# 02_Power_path.net
KiCad netlist of a schematic drawn in Altium Designer
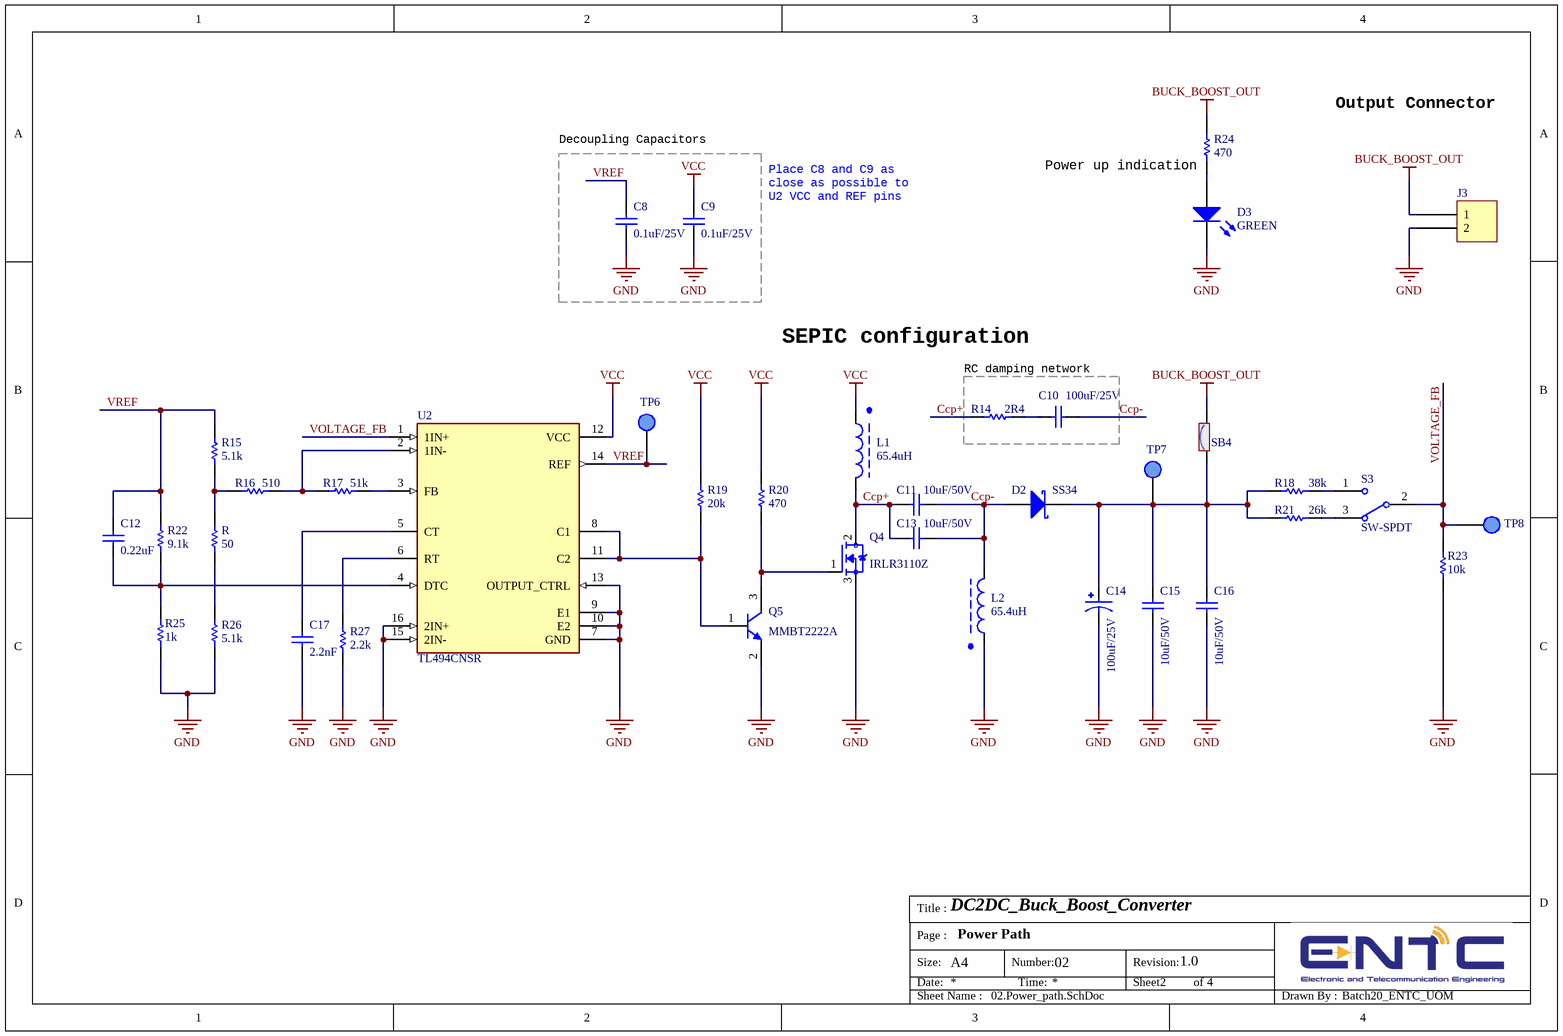
[diagram p0: 02.Power_path.SchDoc]

(export (version "E")
  (design (tool "Eeschema 10.0.6"))
  (components
    (comp (ref "C8")
      (value "0.1uF/25V")
      (footprint "cap0805")
      (fields (field (name "MF") "KYOCERA AVX") (field (name "MP") "08053C104K4Z2A"))
      (libsource (lib "Altium_Main_Library") (part "Cap"))
    )
    (comp (ref "C9")
      (value "0.1uF/25V")
      (footprint "cap0805")
      (fields (field (name "MF") "KYOCERA AVX") (field (name "MP") "08053C104K4Z2A"))
      (libsource (lib "Altium_Main_Library") (part "Cap"))
    )
    (comp (ref "C10")
      (value "100uF/25V")
      (footprint "cap0805")
      (description "Capacitor")
      (libsource (lib "Altium_Main_Library") (part "Cap"))
    )
    (comp (ref "C11")
      (value "10uF/50V")
      (footprint "cap0805")
      (description "Multilayer Ceramic Capacitors MLCC - SMD/SMT 10 uF 50 VDC 10% 0805 X5R")
      (fields (field (name "MF") "Murata Electronics") (field (name "MP") "GRM21BR61H106KE43L"))
      (libsource (lib "Altium_Main_Library") (part "Cap"))
    )
    (comp (ref "C12")
      (value "0.22uF")
      (footprint "cap0805")
      (fields (field (name "MF") "KYOCERA AVX") (field (name "MP") "08055C224KAT2A"))
      (libsource (lib "Altium_Main_Library") (part "Cap"))
    )
    (comp (ref "C13")
      (value "10uF/50V")
      (footprint "cap0805")
      (description "Multilayer Ceramic Capacitors MLCC - SMD/SMT 10 uF 50 VDC 10% 0805 X5R")
      (fields (field (name "MF") "Murata Electronics") (field (name "MP") "GRM21BR61H106KE43L"))
      (libsource (lib "Altium_Main_Library") (part "Cap"))
    )
    (comp (ref "C14")
      (value "100uF/25V")
      (footprint "CAP_EEEFC0J680P")
      (description "Aluminum Electrolytic Capacitors - SMD WCAP-ASLU 100uF 25V 20% SMD/SMT")
      (fields (field (name "MP") "865090449009") (field (name "MF") "Wurth Elektronik"))
      (libsource (lib "Altium_Main_Library") (part "Cap Pol"))
    )
    (comp (ref "C15")
      (value "10uF/50V")
      (footprint "cap0805")
      (description "Multilayer Ceramic Capacitors MLCC - SMD/SMT 10 uF 50 VDC 10% 0805 X5R")
      (fields (field (name "MF") "Murata Electronics") (field (name "MP") "GRM21BR61H106KE43L"))
      (libsource (lib "Altium_Main_Library") (part "Cap"))
    )
    (comp (ref "C16")
      (value "10uF/50V")
      (footprint "cap0805")
      (description "Multilayer Ceramic Capacitors MLCC - SMD/SMT 10 uF 50 VDC 10% 0805 X5R")
      (fields (field (name "MF") "Murata Electronics") (field (name "MP") "GRM21BR61H106KE43L"))
      (libsource (lib "Altium_Main_Library") (part "Cap"))
    )
    (comp (ref "C17")
      (value "2.2nF")
      (footprint "cap0805")
      (fields (field (name "MF") "KYOCERA AVX") (field (name "MP") "08055C222J4T2A"))
      (libsource (lib "Altium_Main_Library") (part "Cap"))
    )
    (comp (ref "D2")
      (value "SS34")
      (footprint "DIO_SS34")
      (description "Schottky Diodes & Rectifiers 40V 3A")
      (fields (field (name "MP") "B340-13-F") (field (name "MF") "Diodes Incorporated"))
      (libsource (lib "DC2DC_Buck_Boost_Converter_SchLib") (part "D Schottky"))
    )
    (comp (ref "D3")
      (value "GREEN")
      (footprint "LED0805")
      (description "Standard LEDs - SMD Ultra Green, 574nm 2.2V, 45mcd")
      (fields (field (name "MP") "SML-LX0805SUGC-TR") (field (name "MF") "Lumex"))
      (libsource (lib "Altium_Main_Library") (part "LED"))
    )
    (comp (ref "J3")
      (value "~")
      (footprint "JST XH B2B-XH-A")
      (description "Barrier Terminal Blocks NC6-P108-02")
      (fields (field (name "MP") "NC6-P108-02") (field (name "MF") "TE Connectivity"))
      (libsource (lib "Altium_Main_Library") (part "2 Pin"))
    )
    (comp (ref "L1")
      (value "65.4uH")
      (footprint "toroid-16x8")
      (description "Inductor")
      (libsource (lib "DC2DC_Buck_Boost_Converter_SchLib") (part "Inductor-ferrite core"))
    )
    (comp (ref "L2")
      (value "65.4uH")
      (footprint "toroid-16x8")
      (description "Inductor")
      (libsource (lib "DC2DC_Buck_Boost_Converter_SchLib") (part "Inductor-ferrite core"))
    )
    (comp (ref "Q4")
      (value "IRLR3110Z")
      (footprint "TO252")
      (description "MOSFETs MOSFT 100V 63A 14mOhm 34nC Log Lvl")
      (fields (field (name "MP") "IRLR3110ZTRLPBF") (field (name "MF") "Infineon Technologies"))
      (libsource (lib "DC2DC_Buck_Boost_Converter_SchLib") (part "IRLR3110Z"))
    )
    (comp (ref "Q5")
      (value "MMBT2222A")
      (footprint "SOT23")
      (description "Bipolar Transistors - BJT BJT, SOT-23, 40V, 600mA, NPN")
      (fields (field (name "MF") "Diotec Semiconductor"))
      (libsource (lib "Altium_Main_Library") (part "NPN"))
    )
    (comp (ref "R")
      (value "50")
      (footprint "RES0402")
      (description "Resistor")
      (libsource (lib "Altium_Main_Library") (part "Res"))
    )
    (comp (ref "R14")
      (value "2R4")
      (footprint "RES0805")
      (description "Thick Film Resistors - SMD 1/4W 0.05 2.4R")
      (fields (field (name "MP") "CRCW08052R40FKEA") (field (name "MF") "Vishay / Dale"))
      (libsource (lib "Altium_Main_Library") (part "Res"))
    )
    (comp (ref "R15")
      (value "5.1k")
      (footprint "RES0805")
      (description "Thick Film Resistors - SMD 5.1Kohms 1% 100ppm")
      (fields (field (name "MP") "RCA08055K10FKEA") (field (name "MF") "Vishay / Draloric"))
      (libsource (lib "Altium_Main_Library") (part "Res"))
    )
    (comp (ref "R16")
      (value "510")
      (footprint "RES0805")
      (description "Thick Film Resistors - SMD 510ohm 5%")
      (fields (field (name "MP") "CR0805-JW-511ELF") (field (name "MF") "Bourns"))
      (libsource (lib "Altium_Main_Library") (part "Res"))
    )
    (comp (ref "R17")
      (value "51k")
      (footprint "RES0805")
      (description "Thick Film Resistors - SMD 51K 1%")
      (fields (field (name "MP") "CR0805-FX-5102ELF") (field (name "MF") "Bourns"))
      (libsource (lib "Altium_Main_Library") (part "Res"))
    )
    (comp (ref "R18")
      (value "38k")
      (footprint "RES0805")
      (description "Thick Film Resistors - SMD CRCW0805 38K 1% 100 RT1")
      (fields (field (name "MP") "CRCW080538K0FKTA") (field (name "MF") "Vishay / Dale"))
      (libsource (lib "Altium_Main_Library") (part "Res"))
    )
    (comp (ref "R19")
      (value "20k")
      (footprint "RES0805")
      (description "Thick Film Resistors - SMD 20K 1%")
      (fields (field (name "MP") "CR0805-FX-2002ELF") (field (name "MF") "Bourns"))
      (libsource (lib "Altium_Main_Library") (part "Res"))
    )
    (comp (ref "R20")
      (value "470")
      (footprint "res1206")
      (description "Thick Film Resistors - SMD 470ohm 5%")
      (fields (field (name "MP") "CR1206-JW-471ELF") (field (name "MF") "Bourns"))
      (libsource (lib "Altium_Main_Library") (part "Res"))
    )
    (comp (ref "R21")
      (value "26k")
      (footprint "RES0805")
      (description "Thick Film Resistors - SMD 26.1K 1%")
      (fields (field (name "MP") "CR0805-FX-2612ELF") (field (name "MF") "Bourns"))
      (libsource (lib "Altium_Main_Library") (part "Res"))
    )
    (comp (ref "R22")
      (value "9.1k")
      (footprint "RES0805")
      (description "Thick Film Resistors - SMD 9.1K 1%")
      (fields (field (name "MP") "CR0805-FX-9101ELF") (field (name "MF") "Bourns"))
      (libsource (lib "Altium_Main_Library") (part "Res"))
    )
    (comp (ref "R23")
      (value "10k")
      (footprint "RES0805")
      (description "Thin Film Resistors - SMD ResThinFilm 0805 10kR 0.5% 125mW TC25")
      (fields (field (name "MP") "CRT0805ADY-1002ELF") (field (name "MF") "Bourns"))
      (libsource (lib "Altium_Main_Library") (part "Res"))
    )
    (comp (ref "R24")
      (value "470")
      (footprint "RES0805")
      (description "Thick Film Resistors - SMD 470ohm 5%")
      (fields (field (name "MP") "CR0805-JW-471ELF") (field (name "MF") "Bourns"))
      (libsource (lib "Altium_Main_Library") (part "Res"))
    )
    (comp (ref "R25")
      (value "1k")
      (footprint "RES0805")
      (description "Thick Film Resistors - SMD 1 kOhms 125 mW 0805 1%")
      (fields (field (name "MP") "RC0805FR-071KL") (field (name "MF") "YAGEO"))
      (libsource (lib "Altium_Main_Library") (part "Res"))
    )
    (comp (ref "R26")
      (value "5.1k")
      (footprint "RES0805")
      (description "Thick Film Resistors - SMD 5.1Kohms 1% 100ppm")
      (fields (field (name "MP") "RCA08055K10FKEA") (field (name "MF") "Vishay / Draloric"))
      (libsource (lib "Altium_Main_Library") (part "Res"))
    )
    (comp (ref "R27")
      (value "2.2k")
      (footprint "RES0805")
      (description "Thin Film Resistors - SMD 2.2K ohm 1% 50 ppm Thin Film")
      (fields (field (name "MP") "RT0805FRE132K2L") (field (name "MF") "YAGEO"))
      (libsource (lib "Altium_Main_Library") (part "Res"))
    )
    (comp (ref "S3")
      (value "SW-SPDT")
      (footprint "SS12D00G3")
      (description "SPDT switch")
      (libsource (lib "DC2DC_Buck_Boost_Converter_SchLib") (part "SW-SPDT"))
    )
    (comp (ref "SB4")
      (value "SB_ON")
      (footprint "SOLDER-BRIDGE_R0805-0R")
      (description "Solder Bridge ON")
      (fields (field (name "MP") "CR0805AJ/-000EAS") (field (name "MF") "Bourns"))
      (libsource (lib "Altium_Main_Library") (part "SB_ON"))
    )
    (comp (ref "TP6")
      (value "VREF")
      (footprint "tp")
      (description "Test Point")
      (libsource (lib "Altium_Main_Library") (part "TP"))
    )
    (comp (ref "TP7")
      (value "~")
      (footprint "tp")
      (description "Test Point")
      (libsource (lib "Altium_Main_Library") (part "TP"))
    )
    (comp (ref "TP8")
      (value "~")
      (footprint "tp")
      (description "Test Point")
      (libsource (lib "Altium_Main_Library") (part "TP"))
    )
    (comp (ref "U2")
      (value "TL494CNSR")
      (footprint "SOIC127P780X200-16N")
      (description "Switching Controllers PWM Controller")
      (fields (field (name "MF") "Texas Instruments"))
      (libsource (lib "DC2DC_Buck_Boost_Converter_SchLib") (part "TL494CNSR"))
    )
  )
  (nets
    (net (code "1") (name "/Ccp+") (class "Default")
      (node (ref "C11") (pin "2") (pinfunction "2_2") (pintype "passive"))
      (node (ref "C13") (pin "2") (pinfunction "2_2") (pintype "passive"))
      (node (ref "L1") (pin "2") (pinfunction "2_2") (pintype "passive"))
      (node (ref "Q4") (pin "2") (pinfunction "D_2") (pintype "passive"))
      (node (ref "R14") (pin "2") (pinfunction "2_2") (pintype "passive"))
    )
    (net (code "2") (name "/Ccp-") (class "Default")
      (node (ref "C10") (pin "1") (pinfunction "1_1") (pintype "passive"))
      (node (ref "C11") (pin "1") (pinfunction "1_1") (pintype "passive"))
      (node (ref "C13") (pin "1") (pinfunction "1_1") (pintype "passive"))
      (node (ref "D2") (pin "1") (pinfunction "A_1") (pintype "passive"))
      (node (ref "L2") (pin "2") (pinfunction "2_2") (pintype "passive"))
    )
    (net (code "3") (name "/VOLTAGE_FB") (class "Default")
      (node (ref "R23") (pin "2") (pinfunction "2_2") (pintype "passive"))
      (node (ref "S3") (pin "2") (pinfunction "2_2") (pintype "passive"))
      (node (ref "TP8") (pin "1") (pinfunction "___TP_1") (pintype "passive"))
      (node (ref "U2") (pin "1") (pinfunction "1IN+_1") (pintype "input"))
    )
    (net (code "4") (name "/VREF") (class "Default")
      (node (ref "C12") (pin "1") (pinfunction "1_1") (pintype "passive"))
      (node (ref "C8") (pin "2") (pinfunction "2_2") (pintype "passive"))
      (node (ref "R15") (pin "2") (pinfunction "2_2") (pintype "passive"))
      (node (ref "R22") (pin "2") (pinfunction "2_2") (pintype "passive"))
      (node (ref "TP6") (pin "1") (pinfunction "___TP_1") (pintype "passive"))
      (node (ref "U2") (pin "14") (pinfunction "REF_14") (pintype "output"))
    )
    (net (code "5") (name "BUCK_BOOST_OUT") (class "Default")
      (node (ref "J3") (pin "1") (pinfunction "1_1") (pintype "passive"))
      (node (ref "R24") (pin "2") (pinfunction "2_2") (pintype "passive"))
      (node (ref "SB4") (pin "2") (pinfunction "2_2") (pintype "passive"))
    )
    (net (code "6") (name "GND") (class "Default")
      (node (ref "C14") (pin "2") (pinfunction "2_2") (pintype "passive"))
      (node (ref "C15") (pin "2") (pinfunction "2_2") (pintype "passive"))
      (node (ref "C16") (pin "2") (pinfunction "2_2") (pintype "passive"))
      (node (ref "C17") (pin "2") (pinfunction "2_2") (pintype "passive"))
      (node (ref "C8") (pin "1") (pinfunction "1_1") (pintype "passive"))
      (node (ref "C9") (pin "1") (pinfunction "1_1") (pintype "passive"))
      (node (ref "D3") (pin "2") (pinfunction "K_2") (pintype "passive"))
      (node (ref "J3") (pin "2") (pinfunction "2_2") (pintype "passive"))
      (node (ref "L2") (pin "1") (pinfunction "1_1") (pintype "passive"))
      (node (ref "Q4") (pin "3") (pinfunction "S_3") (pintype "passive"))
      (node (ref "Q5") (pin "2") (pinfunction "E_2") (pintype "passive"))
      (node (ref "R23") (pin "1") (pinfunction "1_1") (pintype "passive"))
      (node (ref "R25") (pin "1") (pinfunction "1_1") (pintype "passive"))
      (node (ref "R26") (pin "1") (pinfunction "1_1") (pintype "passive"))
      (node (ref "R27") (pin "1") (pinfunction "1_1") (pintype "passive"))
      (node (ref "U2") (pin "10") (pinfunction "E2_10") (pintype "passive"))
      (node (ref "U2") (pin "13") (pinfunction "OUTPUT_CTRL_13") (pintype "input"))
      (node (ref "U2") (pin "15") (pinfunction "2IN-_15") (pintype "input"))
      (node (ref "U2") (pin "16") (pinfunction "2IN+_16") (pintype "input"))
      (node (ref "U2") (pin "7") (pinfunction "GND_7") (pintype "power_in"))
      (node (ref "U2") (pin "9") (pinfunction "E1_9") (pintype "passive"))
    )
    (net (code "7") (name "Net-(C10-Pad2)") (class "Default")
      (node (ref "C10") (pin "2") (pinfunction "2_2") (pintype "passive"))
      (node (ref "R14") (pin "1") (pinfunction "1_1") (pintype "passive"))
    )
    (net (code "8") (name "Net-(D2-K)") (class "Default")
      (node (ref "C14") (pin "1") (pinfunction "1_1") (pintype "passive"))
      (node (ref "C15") (pin "1") (pinfunction "1_1") (pintype "passive"))
      (node (ref "C16") (pin "1") (pinfunction "1_1") (pintype "passive"))
      (node (ref "D2") (pin "2") (pinfunction "K_2") (pintype "passive"))
      (node (ref "R18") (pin "2") (pinfunction "2_2") (pintype "passive"))
      (node (ref "R21") (pin "2") (pinfunction "2_2") (pintype "passive"))
      (node (ref "SB4") (pin "1") (pinfunction "1_1") (pintype "passive"))
      (node (ref "TP7") (pin "1") (pinfunction "___TP_1") (pintype "passive"))
    )
    (net (code "9") (name "Net-(D3-A)") (class "Default")
      (node (ref "D3") (pin "1") (pinfunction "A_1") (pintype "passive"))
      (node (ref "R24") (pin "1") (pinfunction "1_1") (pintype "passive"))
    )
    (net (code "10") (name "Net-(Q4-G)") (class "Default")
      (node (ref "Q4") (pin "1") (pinfunction "G_1") (pintype "passive"))
      (node (ref "Q5") (pin "3") (pinfunction "C_3") (pintype "passive"))
      (node (ref "R20") (pin "1") (pinfunction "1_1") (pintype "passive"))
    )
    (net (code "11") (name "Net-(Q5-B)") (class "Default")
      (node (ref "Q5") (pin "1") (pinfunction "B_1") (pintype "passive"))
      (node (ref "R19") (pin "2") (pinfunction "2_2") (pintype "passive"))
      (node (ref "U2") (pin "11") (pinfunction "C2_11") (pintype "open_collector"))
      (node (ref "U2") (pin "8") (pinfunction "C1_8") (pintype "open_collector"))
    )
    (net (code "12") (name "Net-(R-Pad1)") (class "Default")
      (node (ref "R") (pin "1") (pinfunction "1_1") (pintype "passive"))
      (node (ref "R26") (pin "2") (pinfunction "2_2") (pintype "passive"))
    )
    (net (code "13") (name "Net-(R-Pad2)") (class "Default")
      (node (ref "R") (pin "2") (pinfunction "2_2") (pintype "passive"))
      (node (ref "R15") (pin "1") (pinfunction "1_1") (pintype "passive"))
      (node (ref "R16") (pin "2") (pinfunction "2_2") (pintype "passive"))
    )
    (net (code "14") (name "Net-(R18-Pad1)") (class "Default")
      (node (ref "R18") (pin "1") (pinfunction "1_1") (pintype "passive"))
      (node (ref "S3") (pin "1") (pinfunction "1_1") (pintype "passive"))
    )
    (net (code "15") (name "Net-(R21-Pad1)") (class "Default")
      (node (ref "R21") (pin "1") (pinfunction "1_1") (pintype "passive"))
      (node (ref "S3") (pin "3") (pinfunction "3_3") (pintype "passive"))
    )
    (net (code "16") (name "Net-(U2-1IN-)") (class "Default")
      (node (ref "R16") (pin "1") (pinfunction "1_1") (pintype "passive"))
      (node (ref "R17") (pin "2") (pinfunction "2_2") (pintype "passive"))
      (node (ref "U2") (pin "2") (pinfunction "1IN-_2") (pintype "input"))
    )
    (net (code "17") (name "Net-(U2-CT)") (class "Default")
      (node (ref "C17") (pin "1") (pinfunction "1_1") (pintype "passive"))
      (node (ref "U2") (pin "5") (pinfunction "CT_5") (pintype "passive"))
    )
    (net (code "18") (name "Net-(U2-DTC)") (class "Default")
      (node (ref "C12") (pin "2") (pinfunction "2_2") (pintype "passive"))
      (node (ref "R22") (pin "1") (pinfunction "1_1") (pintype "passive"))
      (node (ref "R25") (pin "2") (pinfunction "2_2") (pintype "passive"))
      (node (ref "U2") (pin "4") (pinfunction "DTC_4") (pintype "input"))
    )
    (net (code "19") (name "Net-(U2-FB)") (class "Default")
      (node (ref "R17") (pin "1") (pinfunction "1_1") (pintype "passive"))
      (node (ref "U2") (pin "3") (pinfunction "FB_3") (pintype "input"))
    )
    (net (code "20") (name "Net-(U2-RT)") (class "Default")
      (node (ref "R27") (pin "2") (pinfunction "2_2") (pintype "passive"))
      (node (ref "U2") (pin "6") (pinfunction "RT_6") (pintype "passive"))
    )
    (net (code "21") (name "VCC") (class "Default")
      (node (ref "C9") (pin "2") (pinfunction "2_2") (pintype "passive"))
      (node (ref "L1") (pin "1") (pinfunction "1_1") (pintype "passive"))
      (node (ref "R19") (pin "1") (pinfunction "1_1") (pintype "passive"))
      (node (ref "R20") (pin "2") (pinfunction "2_2") (pintype "passive"))
      (node (ref "U2") (pin "12") (pinfunction "VCC_12") (pintype "power_in"))
    )
  )
)
